# INTAN_Interface.net
KiCad netlist of a schematic drawn in Altium Designer
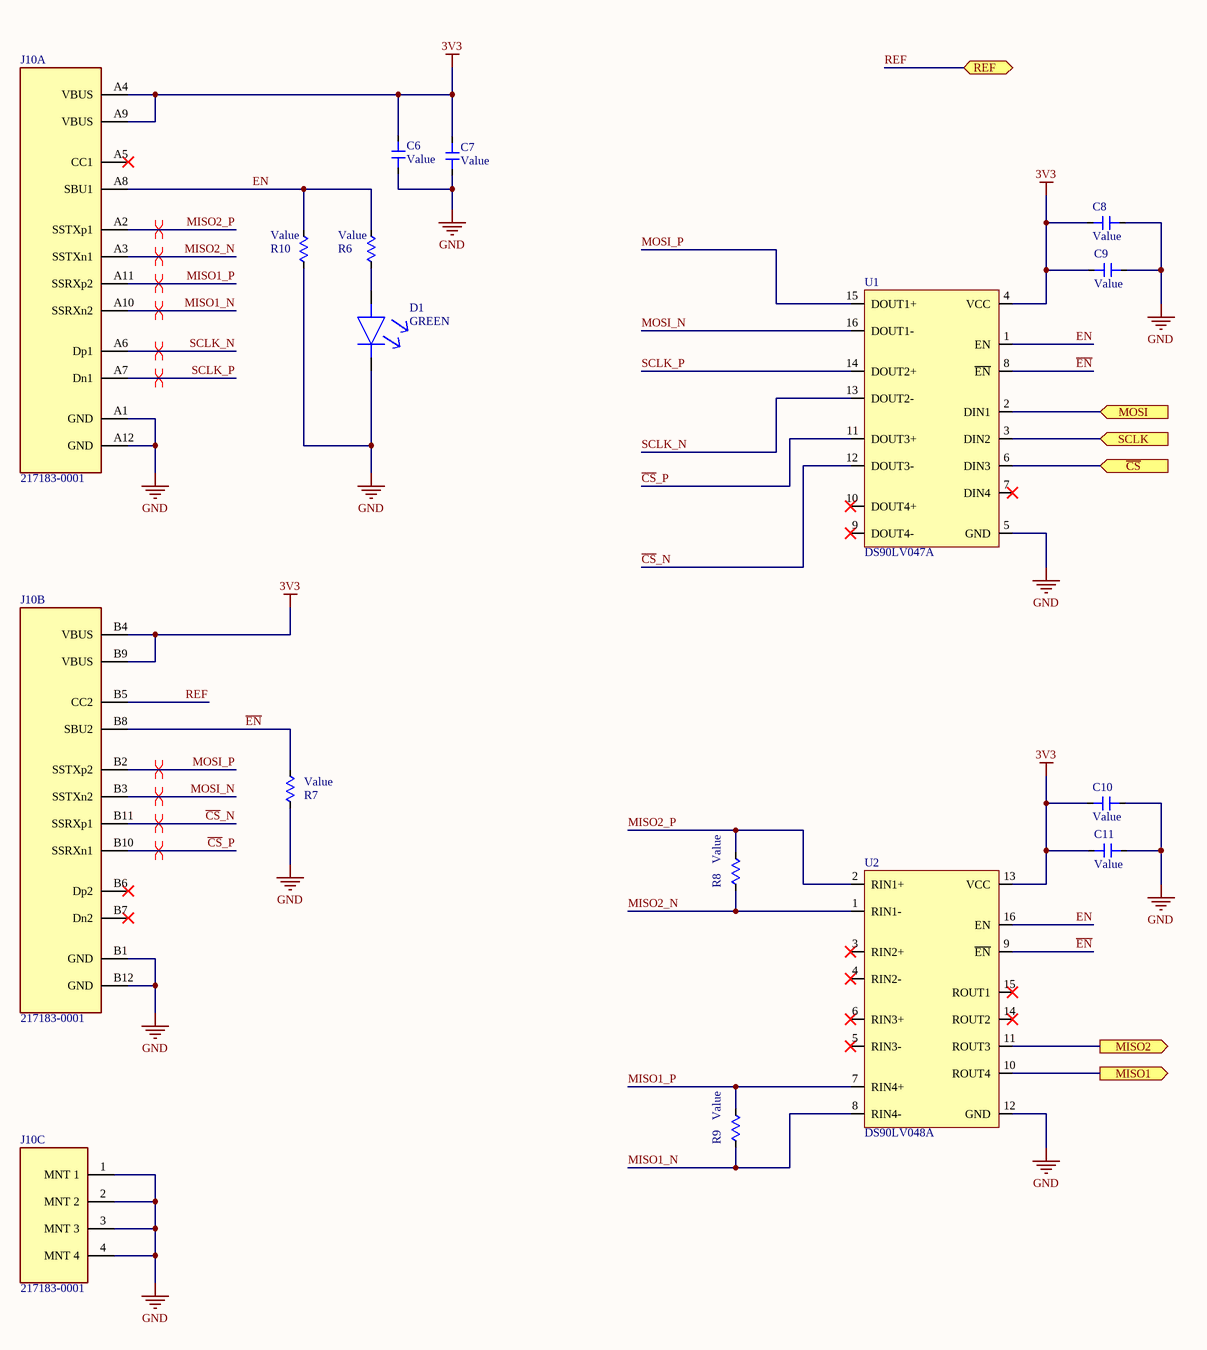
[diagram p0: INTAN_Interface.SchDoc]

(export (version "E")
  (design (tool "Eeschema 10.0.6"))
  (components
    (comp (ref "C6")
      (value "Value")
      (footprint "0603_CAPACITOR")
      (description "Capacitor")
      (libsource (lib "UHDEMG") (part "Capacitor"))
    )
    (comp (ref "C7")
      (value "Value")
      (footprint "0603_CAPACITOR")
      (description "Capacitor")
      (libsource (lib "UHDEMG") (part "Capacitor"))
    )
    (comp (ref "C8")
      (value "Value")
      (footprint "0603_CAPACITOR")
      (description "Capacitor")
      (libsource (lib "UHDEMG") (part "Capacitor"))
    )
    (comp (ref "C9")
      (value "Value")
      (footprint "0603_CAPACITOR")
      (description "Capacitor")
      (libsource (lib "UHDEMG") (part "Capacitor"))
    )
    (comp (ref "C10")
      (value "Value")
      (footprint "0603_CAPACITOR")
      (description "Capacitor")
      (libsource (lib "UHDEMG") (part "Capacitor"))
    )
    (comp (ref "C11")
      (value "Value")
      (footprint "0603_CAPACITOR")
      (description "Capacitor")
      (libsource (lib "UHDEMG") (part "Capacitor"))
    )
    (comp (ref "D1")
      (value "GREEN")
      (footprint "LED_APT1608LZGCK")
      (description "GREEN LED")
      (libsource (lib "UHDEMG") (part "LED_GREEN"))
    )
    (comp (ref "J10")
      (value "217183-0001")
      (footprint "CON_USB_C_SMD")
      (libsource (lib "UHDEMG") (part "CON_USBC_TH_SMT"))
    )
    (comp (ref "R6")
      (value "Value")
      (footprint "0603_RESISTOR")
      (description "Resistor")
      (libsource (lib "UHDEMG") (part "Resistor"))
    )
    (comp (ref "R7")
      (value "Value")
      (footprint "0603_RESISTOR")
      (description "Resistor")
      (libsource (lib "UHDEMG") (part "Resistor"))
    )
    (comp (ref "R8")
      (value "Value")
      (footprint "0402_Resistor")
      (description "Resistor")
      (libsource (lib "UHDEMG") (part "Resistor"))
    )
    (comp (ref "R9")
      (value "Value")
      (footprint "0402_Resistor")
      (description "Resistor")
      (libsource (lib "UHDEMG") (part "Resistor"))
    )
    (comp (ref "R10")
      (value "Value")
      (footprint "0603_RESISTOR")
      (description "Resistor")
      (libsource (lib "UHDEMG") (part "Resistor"))
    )
    (comp (ref "U1")
      (value "DS90LV047A")
      (footprint "TTSOP_16")
      (description "LVDS Transceiver 4 Channels with Enable")
      (libsource (lib "UHDEMG") (part "IC_LVDS_TX4"))
    )
    (comp (ref "U2")
      (value "DS90LV048A")
      (footprint "TTSOP_16")
      (description "LVDS Receiver 4 Channels with Enable")
      (libsource (lib "UHDEMG") (part "IC_LVDS_RX4"))
    )
  )
  (nets
    (net (code "1") (name "/EN") (class "Default")
      (node (ref "J10") (pin "A8") (pinfunction "SBU1_A8") (pintype "passive"))
      (node (ref "R10") (pin "2") (pinfunction "2_2") (pintype "passive"))
      (node (ref "R6") (pin "2") (pinfunction "2_2") (pintype "passive"))
      (node (ref "U1") (pin "1") (pinfunction "EN_1") (pintype "passive"))
      (node (ref "U2") (pin "16") (pinfunction "EN_16") (pintype "passive"))
    )
    (net (code "2") (name "/MISO1") (class "Default")
      (node (ref "U2") (pin "10") (pinfunction "ROUT4_10") (pintype "passive"))
    )
    (net (code "3") (name "/MISO1_N") (class "Default")
      (node (ref "J10") (pin "A10") (pinfunction "SSRXn2_A10") (pintype "passive"))
      (node (ref "R9") (pin "1") (pinfunction "1_1") (pintype "passive"))
      (node (ref "U2") (pin "8") (pinfunction "RIN4-_8") (pintype "passive"))
    )
    (net (code "4") (name "/MISO1_P") (class "Default")
      (node (ref "J10") (pin "A11") (pinfunction "SSRXp2_A11") (pintype "passive"))
      (node (ref "R9") (pin "2") (pinfunction "2_2") (pintype "passive"))
      (node (ref "U2") (pin "7") (pinfunction "RIN4+_7") (pintype "passive"))
    )
    (net (code "5") (name "/MISO2") (class "Default")
      (node (ref "U2") (pin "11") (pinfunction "ROUT3_11") (pintype "passive"))
    )
    (net (code "6") (name "/MISO2_N") (class "Default")
      (node (ref "J10") (pin "A3") (pinfunction "SSTXn1_A3") (pintype "passive"))
      (node (ref "R8") (pin "1") (pinfunction "1_1") (pintype "passive"))
      (node (ref "U2") (pin "1") (pinfunction "RIN1-_1") (pintype "passive"))
    )
    (net (code "7") (name "/MISO2_P") (class "Default")
      (node (ref "J10") (pin "A2") (pinfunction "SSTXp1_A2") (pintype "passive"))
      (node (ref "R8") (pin "2") (pinfunction "2_2") (pintype "passive"))
      (node (ref "U2") (pin "2") (pinfunction "RIN1+_2") (pintype "passive"))
    )
    (net (code "8") (name "/MOSI") (class "Default")
      (node (ref "U1") (pin "2") (pinfunction "DIN1_2") (pintype "passive"))
    )
    (net (code "9") (name "/MOSI_N") (class "Default")
      (node (ref "J10") (pin "B3") (pinfunction "SSTXn2_B3") (pintype "passive"))
      (node (ref "U1") (pin "16") (pinfunction "DOUT1-_16") (pintype "passive"))
    )
    (net (code "10") (name "/MOSI_P") (class "Default")
      (node (ref "J10") (pin "B2") (pinfunction "SSTXp2_B2") (pintype "passive"))
      (node (ref "U1") (pin "15") (pinfunction "DOUT1+_15") (pintype "passive"))
    )
    (net (code "11") (name "/REF") (class "Default")
      (node (ref "J10") (pin "B5") (pinfunction "CC2_B5") (pintype "passive"))
    )
    (net (code "12") (name "/SCLK") (class "Default")
      (node (ref "U1") (pin "3") (pinfunction "DIN2_3") (pintype "passive"))
    )
    (net (code "13") (name "/SCLK_N") (class "Default")
      (node (ref "J10") (pin "A6") (pinfunction "Dp1_A6") (pintype "passive"))
      (node (ref "U1") (pin "13") (pinfunction "DOUT2-_13") (pintype "passive"))
    )
    (net (code "14") (name "/SCLK_P") (class "Default")
      (node (ref "J10") (pin "A7") (pinfunction "Dn1_A7") (pintype "passive"))
      (node (ref "U1") (pin "14") (pinfunction "DOUT2+_14") (pintype "passive"))
    )
    (net (code "15") (name "/~{CS}") (class "Default")
      (node (ref "U1") (pin "6") (pinfunction "DIN3_6") (pintype "passive"))
    )
    (net (code "16") (name "/~{CS}_N") (class "Default")
      (node (ref "J10") (pin "B11") (pinfunction "SSRXp1_B11") (pintype "passive"))
      (node (ref "U1") (pin "12") (pinfunction "DOUT3-_12") (pintype "passive"))
    )
    (net (code "17") (name "/~{CS}_P") (class "Default")
      (node (ref "J10") (pin "B10") (pinfunction "SSRXn1_B10") (pintype "passive"))
      (node (ref "U1") (pin "11") (pinfunction "DOUT3+_11") (pintype "passive"))
    )
    (net (code "18") (name "/~{EN}") (class "Default")
      (node (ref "J10") (pin "B8") (pinfunction "SBU2_B8") (pintype "passive"))
      (node (ref "R7") (pin "2") (pinfunction "2_2") (pintype "passive"))
      (node (ref "U1") (pin "8") (pinfunction "~{EN}_8") (pintype "passive"))
      (node (ref "U2") (pin "9") (pinfunction "~{EN}_9") (pintype "passive"))
    )
    (net (code "19") (name "3V3") (class "Default")
      (node (ref "C10") (pin "1") (pinfunction "1_1") (pintype "passive"))
      (node (ref "C11") (pin "1") (pinfunction "1_1") (pintype "passive"))
      (node (ref "C6") (pin "2") (pinfunction "2_2") (pintype "passive"))
      (node (ref "C7") (pin "2") (pinfunction "2_2") (pintype "passive"))
      (node (ref "C8") (pin "1") (pinfunction "1_1") (pintype "passive"))
      (node (ref "C9") (pin "1") (pinfunction "1_1") (pintype "passive"))
      (node (ref "J10") (pin "A4") (pinfunction "VBUS_A4") (pintype "passive"))
      (node (ref "J10") (pin "A9") (pinfunction "VBUS_A9") (pintype "passive"))
      (node (ref "J10") (pin "B4") (pinfunction "VBUS_B4") (pintype "passive"))
      (node (ref "J10") (pin "B9") (pinfunction "VBUS_B9") (pintype "passive"))
      (node (ref "U1") (pin "4") (pinfunction "VCC_4") (pintype "passive"))
      (node (ref "U2") (pin "13") (pinfunction "VCC_13") (pintype "passive"))
    )
    (net (code "20") (name "GND") (class "Default")
      (node (ref "C10") (pin "2") (pinfunction "2_2") (pintype "passive"))
      (node (ref "C11") (pin "2") (pinfunction "2_2") (pintype "passive"))
      (node (ref "C6") (pin "1") (pinfunction "1_1") (pintype "passive"))
      (node (ref "C7") (pin "1") (pinfunction "1_1") (pintype "passive"))
      (node (ref "C8") (pin "2") (pinfunction "2_2") (pintype "passive"))
      (node (ref "C9") (pin "2") (pinfunction "2_2") (pintype "passive"))
      (node (ref "D1") (pin "1") (pinfunction "1_1") (pintype "passive"))
      (node (ref "J10") (pin "1") (pinfunction "MNT_1_1") (pintype "passive"))
      (node (ref "J10") (pin "2") (pinfunction "MNT_2_2") (pintype "passive"))
      (node (ref "J10") (pin "3") (pinfunction "MNT_3_3") (pintype "passive"))
      (node (ref "J10") (pin "4") (pinfunction "MNT_4_4") (pintype "passive"))
      (node (ref "J10") (pin "A1") (pinfunction "GND_A1") (pintype "passive"))
      (node (ref "J10") (pin "A12") (pinfunction "GND_A12") (pintype "passive"))
      (node (ref "J10") (pin "B1") (pinfunction "GND_B1") (pintype "passive"))
      (node (ref "J10") (pin "B12") (pinfunction "GND_B12") (pintype "passive"))
      (node (ref "R10") (pin "1") (pinfunction "1_1") (pintype "passive"))
      (node (ref "R7") (pin "1") (pinfunction "1_1") (pintype "passive"))
      (node (ref "U1") (pin "5") (pinfunction "GND_5") (pintype "passive"))
      (node (ref "U2") (pin "12") (pinfunction "GND_12") (pintype "passive"))
    )
    (net (code "21") (name "Net-(D1-Pad2)") (class "Default")
      (node (ref "D1") (pin "2") (pinfunction "2_2") (pintype "passive"))
      (node (ref "R6") (pin "1") (pinfunction "1_1") (pintype "passive"))
    )
    (net (code "22") (name "unconnected-(J10A-CC1-PadA5)") (class "Default")
      (node (ref "J10") (pin "A5") (pinfunction "CC1_A5") (pintype "passive+no_connect"))
    )
    (net (code "23") (name "unconnected-(J10B-Dn2-PadB7)") (class "Default")
      (node (ref "J10") (pin "B7") (pinfunction "Dn2_B7") (pintype "passive+no_connect"))
    )
    (net (code "24") (name "unconnected-(J10B-Dp2-PadB6)") (class "Default")
      (node (ref "J10") (pin "B6") (pinfunction "Dp2_B6") (pintype "passive+no_connect"))
    )
    (net (code "25") (name "unconnected-(U1-DIN4-Pad7)") (class "Default")
      (node (ref "U1") (pin "7") (pinfunction "DIN4_7") (pintype "passive+no_connect"))
    )
    (net (code "26") (name "unconnected-(U1-DOUT4+-Pad10)") (class "Default")
      (node (ref "U1") (pin "10") (pinfunction "DOUT4+_10") (pintype "passive+no_connect"))
    )
    (net (code "27") (name "unconnected-(U1-DOUT4--Pad9)") (class "Default")
      (node (ref "U1") (pin "9") (pinfunction "DOUT4-_9") (pintype "passive+no_connect"))
    )
    (net (code "28") (name "unconnected-(U2-RIN2+-Pad3)") (class "Default")
      (node (ref "U2") (pin "3") (pinfunction "RIN2+_3") (pintype "passive+no_connect"))
    )
    (net (code "29") (name "unconnected-(U2-RIN2--Pad4)") (class "Default")
      (node (ref "U2") (pin "4") (pinfunction "RIN2-_4") (pintype "passive+no_connect"))
    )
    (net (code "30") (name "unconnected-(U2-RIN3+-Pad6)") (class "Default")
      (node (ref "U2") (pin "6") (pinfunction "RIN3+_6") (pintype "passive+no_connect"))
    )
    (net (code "31") (name "unconnected-(U2-RIN3--Pad5)") (class "Default")
      (node (ref "U2") (pin "5") (pinfunction "RIN3-_5") (pintype "passive+no_connect"))
    )
    (net (code "32") (name "unconnected-(U2-ROUT1-Pad15)") (class "Default")
      (node (ref "U2") (pin "15") (pinfunction "ROUT1_15") (pintype "passive+no_connect"))
    )
    (net (code "33") (name "unconnected-(U2-ROUT2-Pad14)") (class "Default")
      (node (ref "U2") (pin "14") (pinfunction "ROUT2_14") (pintype "passive+no_connect"))
    )
  )
)
